# MB1297_RF_Module.net
KiCad netlist of a schematic drawn in Altium Designer
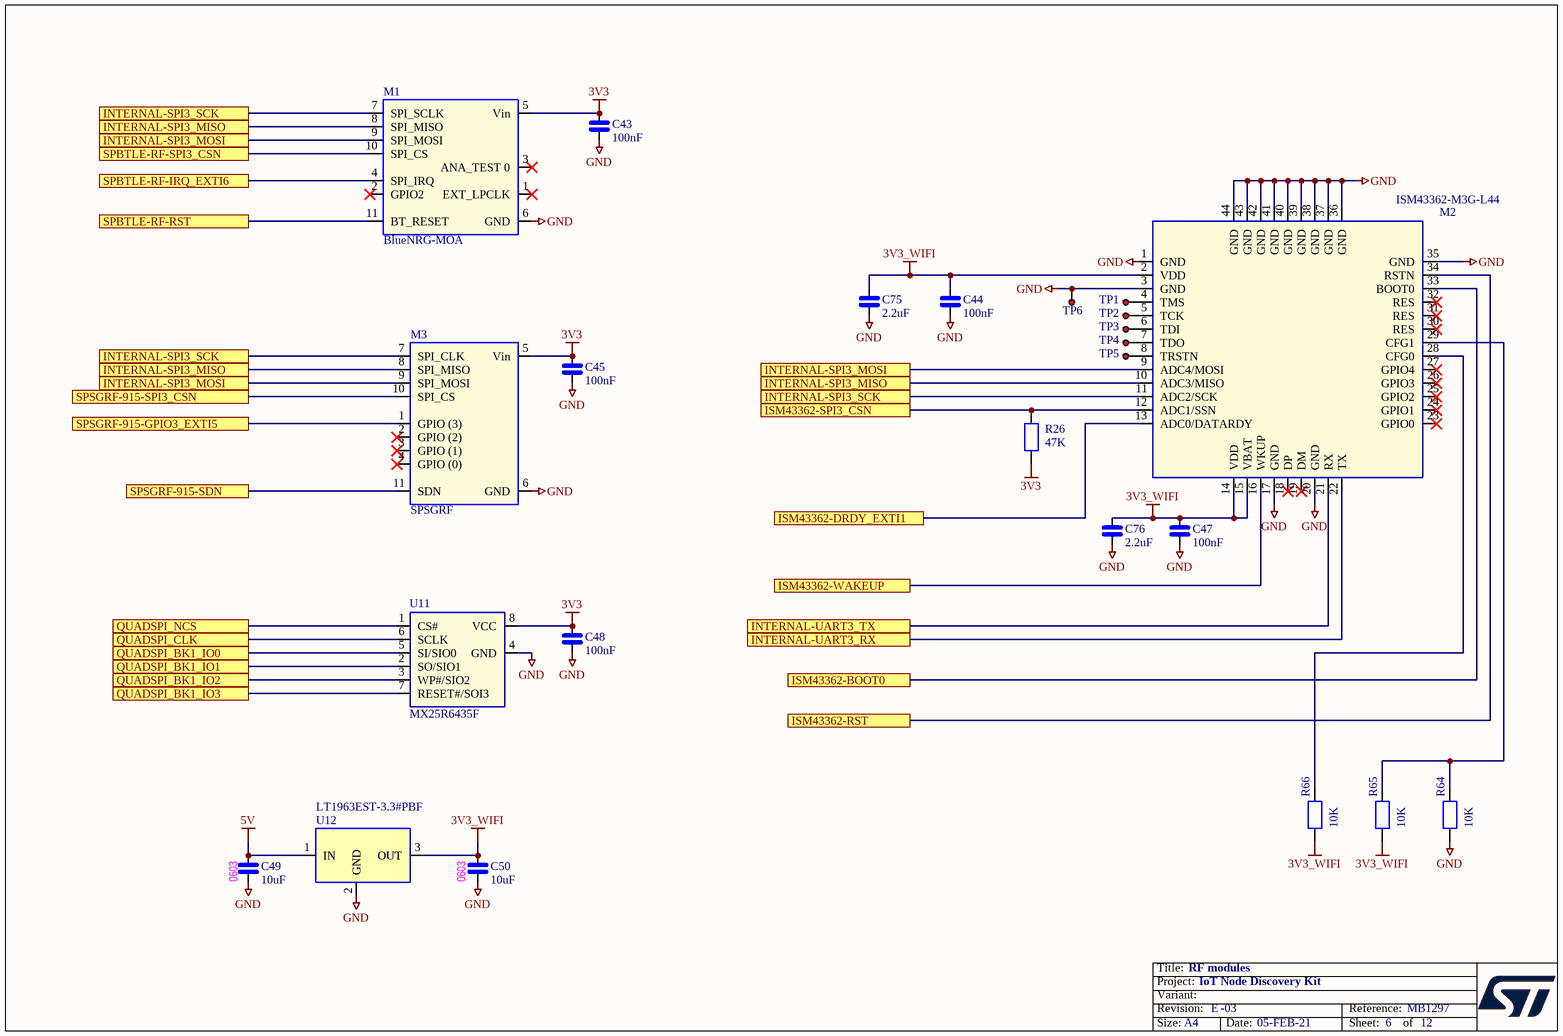
[diagram p0: MB1297_RF_Module.SchDoc]

(export (version "E")
  (design (tool "Eeschema 10.0.6"))
  (components
    (comp (ref "C43")
      (value "100nF")
      (footprint "0402")
      (description "Capacitor_not polarized")
      (libsource (lib "ST_Lib3D") (part "CAP_NPOL"))
    )
    (comp (ref "C44")
      (value "100nF")
      (footprint "0402")
      (description "Capacitor_not polarized")
      (libsource (lib "ST_Lib3D") (part "CAP_NPOL"))
    )
    (comp (ref "C45")
      (value "100nF")
      (footprint "0402")
      (description "Capacitor_not polarized")
      (libsource (lib "ST_Lib3D") (part "CAP_NPOL"))
    )
    (comp (ref "C47")
      (value "100nF")
      (footprint "0402")
      (description "Capacitor_not polarized")
      (libsource (lib "ST_Lib3D") (part "CAP_NPOL"))
    )
    (comp (ref "C48")
      (value "100nF")
      (footprint "0402")
      (description "Capacitor_not polarized")
      (libsource (lib "ST_Lib3D") (part "CAP_NPOL"))
    )
    (comp (ref "C49")
      (value "10uF")
      (footprint "0603_CAP_NPOL")
      (description "Capacitor_not polarized")
      (libsource (lib "ST_Lib3D") (part "CAP_NPOL"))
    )
    (comp (ref "C50")
      (value "10uF")
      (footprint "0603_CAP_NPOL")
      (description "Capacitor_not polarized")
      (libsource (lib "ST_Lib3D") (part "CAP_NPOL"))
    )
    (comp (ref "C75")
      (value "2.2uF")
      (footprint "0603_CAP_NPOL")
      (description "Capacitor_not polarized")
      (libsource (lib "ST_Lib3D") (part "CAP_NPOL"))
    )
    (comp (ref "C76")
      (value "2.2uF")
      (footprint "0603_CAP_NPOL")
      (description "Capacitor_not polarized")
      (libsource (lib "ST_Lib3D") (part "CAP_NPOL"))
    )
    (comp (ref "M1")
      (value "BlueNRG-MOA")
      (footprint "SPBTLE-RF")
      (description "SPBTLE-RF")
      (libsource (lib "MB1297") (part "SPBTLE-RF"))
    )
    (comp (ref "M2")
      (value "ISM43362-M3G-L44")
      (footprint "ISM43362-M3G-L44")
      (description "ISM43362-M3G-L44 Wifi Module 802.11 bgn")
      (libsource (lib "Phil_Lib3D") (part "ISM43362-M3G-L44"))
    )
    (comp (ref "M3")
      (value "SPSGRF")
      (footprint "SPSGRF")
      (description "SPSGRF-915or SPSGRF-868")
      (libsource (lib "MB1297") (part "SPSGRF"))
    )
    (comp (ref "R26")
      (value "47K")
      (footprint "0402")
      (description "Resistor")
      (libsource (lib "Lib3D_Altium10_Schlib") (part "RES"))
    )
    (comp (ref "R64")
      (value "10K")
      (footprint "0402")
      (description "Resistor")
      (libsource (lib "Lib3D_Altium10_Schlib") (part "RES"))
    )
    (comp (ref "R65")
      (value "10K")
      (footprint "0402")
      (description "Resistor")
      (libsource (lib "Lib3D_Altium10_Schlib") (part "RES"))
    )
    (comp (ref "R66")
      (value "10K")
      (footprint "0402")
      (description "Resistor")
      (libsource (lib "Lib3D_Altium10_Schlib") (part "RES"))
    )
    (comp (ref "TP1")
      (value "PT")
      (footprint "PTB")
      (description "Point de test")
      (libsource (lib "ST_Lib2D") (part "PT"))
    )
    (comp (ref "TP2")
      (value "PT")
      (footprint "PTB")
      (description "Point de test")
      (libsource (lib "ST_Lib2D") (part "PT"))
    )
    (comp (ref "TP3")
      (value "PT")
      (footprint "PTB")
      (description "Point de test")
      (libsource (lib "ST_Lib2D") (part "PT"))
    )
    (comp (ref "TP4")
      (value "PT")
      (footprint "PTB")
      (description "Point de test")
      (libsource (lib "ST_Lib2D") (part "PT"))
    )
    (comp (ref "TP5")
      (value "PT")
      (footprint "PTB")
      (description "Point de test")
      (libsource (lib "ST_Lib2D") (part "PT"))
    )
    (comp (ref "TP6")
      (value "PT")
      (footprint "PTB")
      (description "Point de test")
      (libsource (lib "ST_Lib2D") (part "PT"))
    )
    (comp (ref "U11")
      (value "MX25R6435F")
      (footprint "SOP8L")
      (description "MX25R6435F Serial Flash Memory 64M")
      (libsource (lib "ST_Lib3D") (part "MX25R6435F"))
    )
    (comp (ref "U12")
      (value "LT1963EST-3.3#PBF")
      (footprint "ST_Lib3D:SOT223_SC73")
      (description "LT1963EST-3.3 LDO Low Noise 1.5A fast Transient Response")
      (libsource (lib "ST_Lib3D") (part "LT1963EST-3.3"))
    )
  )
  (nets
    (net (code "1") (name "/INTERNAL-SPI3_MISO") (class "Default")
      (node (ref "M1") (pin "8") (pinfunction "SPI_MISO_8") (pintype "passive"))
      (node (ref "M2") (pin "10") (pinfunction "ADC3/MISO_10") (pintype "passive"))
      (node (ref "M3") (pin "8") (pinfunction "SPI_MISO_8") (pintype "passive"))
    )
    (net (code "2") (name "/INTERNAL-SPI3_MOSI") (class "Default")
      (node (ref "M1") (pin "9") (pinfunction "SPI_MOSI_9") (pintype "passive"))
      (node (ref "M2") (pin "9") (pinfunction "ADC4/MOSI_9") (pintype "passive"))
      (node (ref "M3") (pin "9") (pinfunction "SPI_MOSI_9") (pintype "passive"))
    )
    (net (code "3") (name "/INTERNAL-SPI3_SCK") (class "Default")
      (node (ref "M1") (pin "7") (pinfunction "SPI_SCLK_7") (pintype "passive"))
      (node (ref "M2") (pin "11") (pinfunction "ADC2/SCK_11") (pintype "passive"))
      (node (ref "M3") (pin "7") (pinfunction "SPI_CLK_7") (pintype "passive"))
    )
    (net (code "4") (name "/INTERNAL-UART3_RX") (class "Default")
      (node (ref "M2") (pin "22") (pinfunction "TX_22") (pintype "passive"))
    )
    (net (code "5") (name "/INTERNAL-UART3_TX") (class "Default")
      (node (ref "M2") (pin "21") (pinfunction "RX_21") (pintype "passive"))
    )
    (net (code "6") (name "/ISM43362-BOOT0") (class "Default")
      (node (ref "M2") (pin "33") (pinfunction "BOOT0_33") (pintype "passive"))
    )
    (net (code "7") (name "/ISM43362-DRDY_EXTI1") (class "Default")
      (node (ref "M2") (pin "13") (pinfunction "ADC0/DATARDY_13") (pintype "passive"))
    )
    (net (code "8") (name "/ISM43362-RST") (class "Default")
      (node (ref "M2") (pin "34") (pinfunction "RSTN_34") (pintype "passive"))
    )
    (net (code "9") (name "/ISM43362-SPI3_CSN") (class "Default")
      (node (ref "M2") (pin "12") (pinfunction "ADC1/SSN_12") (pintype "passive"))
      (node (ref "R26") (pin "1") (pinfunction "1_1") (pintype "passive"))
    )
    (net (code "10") (name "/ISM43362-WAKEUP") (class "Default")
      (node (ref "M2") (pin "16") (pinfunction "WKUP_16") (pintype "passive"))
    )
    (net (code "11") (name "/QUADSPI_BK1_IO0") (class "Default")
      (node (ref "U11") (pin "5") (pinfunction "SI/SIO0_5") (pintype "passive"))
    )
    (net (code "12") (name "/QUADSPI_BK1_IO1") (class "Default")
      (node (ref "U11") (pin "2") (pinfunction "SO/SIO1_2") (pintype "passive"))
    )
    (net (code "13") (name "/QUADSPI_BK1_IO2") (class "Default")
      (node (ref "U11") (pin "3") (pinfunction "WP#/SIO2_3") (pintype "passive"))
    )
    (net (code "14") (name "/QUADSPI_BK1_IO3") (class "Default")
      (node (ref "U11") (pin "7") (pinfunction "RESET#/SOI3_7") (pintype "passive"))
    )
    (net (code "15") (name "/QUADSPI_CLK") (class "Default")
      (node (ref "U11") (pin "6") (pinfunction "SCLK_6") (pintype "passive"))
    )
    (net (code "16") (name "/QUADSPI_NCS") (class "Default")
      (node (ref "U11") (pin "1") (pinfunction "CS#_1") (pintype "passive"))
    )
    (net (code "17") (name "/SPBTLE-RF-IRQ_EXTI6") (class "Default")
      (node (ref "M1") (pin "4") (pinfunction "SPI_IRQ_4") (pintype "passive"))
    )
    (net (code "18") (name "/SPBTLE-RF-RST") (class "Default")
      (node (ref "M1") (pin "11") (pinfunction "BT_RESET_11") (pintype "passive"))
    )
    (net (code "19") (name "/SPBTLE-RF-SPI3_CSN") (class "Default")
      (node (ref "M1") (pin "10") (pinfunction "SPI_CS_10") (pintype "passive"))
    )
    (net (code "20") (name "/SPSGRF-915-GPIO3_EXTI5") (class "Default")
      (node (ref "M3") (pin "1") (pinfunction "GPIO_(3)_1") (pintype "passive"))
    )
    (net (code "21") (name "/SPSGRF-915-SDN") (class "Default")
      (node (ref "M3") (pin "11") (pinfunction "SDN_11") (pintype "passive"))
    )
    (net (code "22") (name "/SPSGRF-915-SPI3_CSN") (class "Default")
      (node (ref "M3") (pin "10") (pinfunction "SPI_CS_10") (pintype "passive"))
    )
    (net (code "23") (name "3V3") (class "Default")
      (node (ref "C43") (pin "1") (pinfunction "1_1") (pintype "passive"))
      (node (ref "C45") (pin "1") (pinfunction "1_1") (pintype "passive"))
      (node (ref "C48") (pin "1") (pinfunction "1_1") (pintype "passive"))
      (node (ref "M1") (pin "5") (pinfunction "Vin_5") (pintype "passive"))
      (node (ref "M3") (pin "5") (pinfunction "Vin_5") (pintype "passive"))
      (node (ref "R26") (pin "2") (pinfunction "2_2") (pintype "passive"))
      (node (ref "U11") (pin "8") (pinfunction "VCC_8") (pintype "passive"))
    )
    (net (code "24") (name "3V3_WIFI") (class "Default")
      (node (ref "C44") (pin "1") (pinfunction "1_1") (pintype "passive"))
      (node (ref "C47") (pin "1") (pinfunction "1_1") (pintype "passive"))
      (node (ref "C50") (pin "1") (pinfunction "1_1") (pintype "passive"))
      (node (ref "C75") (pin "1") (pinfunction "1_1") (pintype "passive"))
      (node (ref "C76") (pin "1") (pinfunction "1_1") (pintype "passive"))
      (node (ref "M2") (pin "14") (pinfunction "VDD_14") (pintype "passive"))
      (node (ref "M2") (pin "15") (pinfunction "VBAT_15") (pintype "passive"))
      (node (ref "M2") (pin "2") (pinfunction "VDD_2") (pintype "passive"))
      (node (ref "R65") (pin "2") (pinfunction "2_2") (pintype "passive"))
      (node (ref "R66") (pin "2") (pinfunction "2_2") (pintype "passive"))
      (node (ref "U12") (pin "3") (pinfunction "OUT_3") (pintype "passive"))
    )
    (net (code "25") (name "5V") (class "Default")
      (node (ref "C49") (pin "1") (pinfunction "1_1") (pintype "passive"))
      (node (ref "U12") (pin "1") (pinfunction "IN_1") (pintype "passive"))
    )
    (net (code "26") (name "GND") (class "Default")
      (node (ref "C43") (pin "2") (pinfunction "2_2") (pintype "passive"))
      (node (ref "C44") (pin "2") (pinfunction "2_2") (pintype "passive"))
      (node (ref "C45") (pin "2") (pinfunction "2_2") (pintype "passive"))
      (node (ref "C47") (pin "2") (pinfunction "2_2") (pintype "passive"))
      (node (ref "C48") (pin "2") (pinfunction "2_2") (pintype "passive"))
      (node (ref "C49") (pin "2") (pinfunction "2_2") (pintype "passive"))
      (node (ref "C50") (pin "2") (pinfunction "2_2") (pintype "passive"))
      (node (ref "C75") (pin "2") (pinfunction "2_2") (pintype "passive"))
      (node (ref "C76") (pin "2") (pinfunction "2_2") (pintype "passive"))
      (node (ref "M1") (pin "6") (pinfunction "GND_6") (pintype "passive"))
      (node (ref "M2") (pin "1") (pinfunction "GND_1") (pintype "passive"))
      (node (ref "M2") (pin "17") (pinfunction "GND_17") (pintype "passive"))
      (node (ref "M2") (pin "20") (pinfunction "GND_20") (pintype "passive"))
      (node (ref "M2") (pin "3") (pinfunction "GND_3") (pintype "passive"))
      (node (ref "M2") (pin "35") (pinfunction "GND_35") (pintype "passive"))
      (node (ref "M2") (pin "36") (pinfunction "GND_36") (pintype "passive"))
      (node (ref "M2") (pin "37") (pinfunction "GND_37") (pintype "passive"))
      (node (ref "M2") (pin "38") (pinfunction "GND_38") (pintype "passive"))
      (node (ref "M2") (pin "39") (pinfunction "GND_39") (pintype "passive"))
      (node (ref "M2") (pin "40") (pinfunction "GND_40") (pintype "passive"))
      (node (ref "M2") (pin "41") (pinfunction "GND_41") (pintype "passive"))
      (node (ref "M2") (pin "42") (pinfunction "GND_42") (pintype "passive"))
      (node (ref "M2") (pin "43") (pinfunction "GND_43") (pintype "passive"))
      (node (ref "M2") (pin "44") (pinfunction "GND_44") (pintype "passive"))
      (node (ref "M3") (pin "6") (pinfunction "GND_6") (pintype "passive"))
      (node (ref "R64") (pin "2") (pinfunction "2_2") (pintype "passive"))
      (node (ref "TP6") (pin "1") (pintype "passive"))
      (node (ref "U11") (pin "4") (pinfunction "GND_4") (pintype "passive"))
      (node (ref "U12") (pin "2") (pinfunction "GND_2") (pintype "passive"))
    )
    (net (code "27") (name "Net-(M2-CFG0)") (class "Default")
      (node (ref "M2") (pin "28") (pinfunction "CFG0_28") (pintype "passive"))
      (node (ref "R66") (pin "1") (pinfunction "1_1") (pintype "passive"))
    )
    (net (code "28") (name "Net-(M2-CFG1)") (class "Default")
      (node (ref "M2") (pin "29") (pinfunction "CFG1_29") (pintype "passive"))
      (node (ref "R64") (pin "1") (pinfunction "1_1") (pintype "passive"))
      (node (ref "R65") (pin "1") (pinfunction "1_1") (pintype "passive"))
    )
    (net (code "29") (name "Net-(M2-TCK)") (class "Default")
      (node (ref "M2") (pin "5") (pinfunction "TCK_5") (pintype "passive"))
      (node (ref "TP2") (pin "1") (pintype "passive"))
    )
    (net (code "30") (name "Net-(M2-TDI)") (class "Default")
      (node (ref "M2") (pin "6") (pinfunction "TDI_6") (pintype "passive"))
      (node (ref "TP3") (pin "1") (pintype "passive"))
    )
    (net (code "31") (name "Net-(M2-TDO)") (class "Default")
      (node (ref "M2") (pin "7") (pinfunction "TDO_7") (pintype "passive"))
      (node (ref "TP4") (pin "1") (pintype "passive"))
    )
    (net (code "32") (name "Net-(M2-TMS)") (class "Default")
      (node (ref "M2") (pin "4") (pinfunction "TMS_4") (pintype "passive"))
      (node (ref "TP1") (pin "1") (pintype "passive"))
    )
    (net (code "33") (name "Net-(M2-TRSTN)") (class "Default")
      (node (ref "M2") (pin "8") (pinfunction "TRSTN_8") (pintype "passive"))
      (node (ref "TP5") (pin "1") (pintype "passive"))
    )
    (net (code "34") (name "unconnected-(M1-ANA_TEST_0-Pad3)") (class "Default")
      (node (ref "M1") (pin "3") (pinfunction "ANA_TEST_0_3") (pintype "passive+no_connect"))
    )
    (net (code "35") (name "unconnected-(M1-EXT_LPCLK-Pad1)") (class "Default")
      (node (ref "M1") (pin "1") (pinfunction "EXT_LPCLK_1") (pintype "passive+no_connect"))
    )
    (net (code "36") (name "unconnected-(M1-GPIO2-Pad2)") (class "Default")
      (node (ref "M1") (pin "2") (pinfunction "GPIO2_2") (pintype "passive+no_connect"))
    )
    (net (code "37") (name "unconnected-(M2-DM-Pad19)") (class "Default")
      (node (ref "M2") (pin "19") (pinfunction "DM_19") (pintype "passive+no_connect"))
    )
    (net (code "38") (name "unconnected-(M2-DP-Pad18)") (class "Default")
      (node (ref "M2") (pin "18") (pinfunction "DP_18") (pintype "passive+no_connect"))
    )
    (net (code "39") (name "unconnected-(M2-GPIO0-Pad23)") (class "Default")
      (node (ref "M2") (pin "23") (pinfunction "GPIO0_23") (pintype "passive+no_connect"))
    )
    (net (code "40") (name "unconnected-(M2-GPIO1-Pad24)") (class "Default")
      (node (ref "M2") (pin "24") (pinfunction "GPIO1_24") (pintype "passive+no_connect"))
    )
    (net (code "41") (name "unconnected-(M2-GPIO2-Pad25)") (class "Default")
      (node (ref "M2") (pin "25") (pinfunction "GPIO2_25") (pintype "passive+no_connect"))
    )
    (net (code "42") (name "unconnected-(M2-GPIO3-Pad26)") (class "Default")
      (node (ref "M2") (pin "26") (pinfunction "GPIO3_26") (pintype "passive+no_connect"))
    )
    (net (code "43") (name "unconnected-(M2-GPIO4-Pad27)") (class "Default")
      (node (ref "M2") (pin "27") (pinfunction "GPIO4_27") (pintype "passive+no_connect"))
    )
    (net (code "44") (name "unconnected-(M2-RES-Pad30)") (class "Default")
      (node (ref "M2") (pin "30") (pinfunction "RES_30") (pintype "passive+no_connect"))
    )
    (net (code "45") (name "unconnected-(M2-RES-Pad31)") (class "Default")
      (node (ref "M2") (pin "31") (pinfunction "RES_31") (pintype "passive+no_connect"))
    )
    (net (code "46") (name "unconnected-(M2-RES-Pad32)") (class "Default")
      (node (ref "M2") (pin "32") (pinfunction "RES_32") (pintype "passive+no_connect"))
    )
    (net (code "47") (name "unconnected-(M3-GPIO_(0)-Pad4)") (class "Default")
      (node (ref "M3") (pin "4") (pinfunction "GPIO_(0)_4") (pintype "passive+no_connect"))
    )
    (net (code "48") (name "unconnected-(M3-GPIO_(1)-Pad3)") (class "Default")
      (node (ref "M3") (pin "3") (pinfunction "GPIO_(1)_3") (pintype "passive+no_connect"))
    )
    (net (code "49") (name "unconnected-(M3-GPIO_(2)-Pad2)") (class "Default")
      (node (ref "M3") (pin "2") (pinfunction "GPIO_(2)_2") (pintype "passive+no_connect"))
    )
  )
)
